# 6_-H3_MAIN.net
KiCad netlist of a schematic drawn in Altium Designer
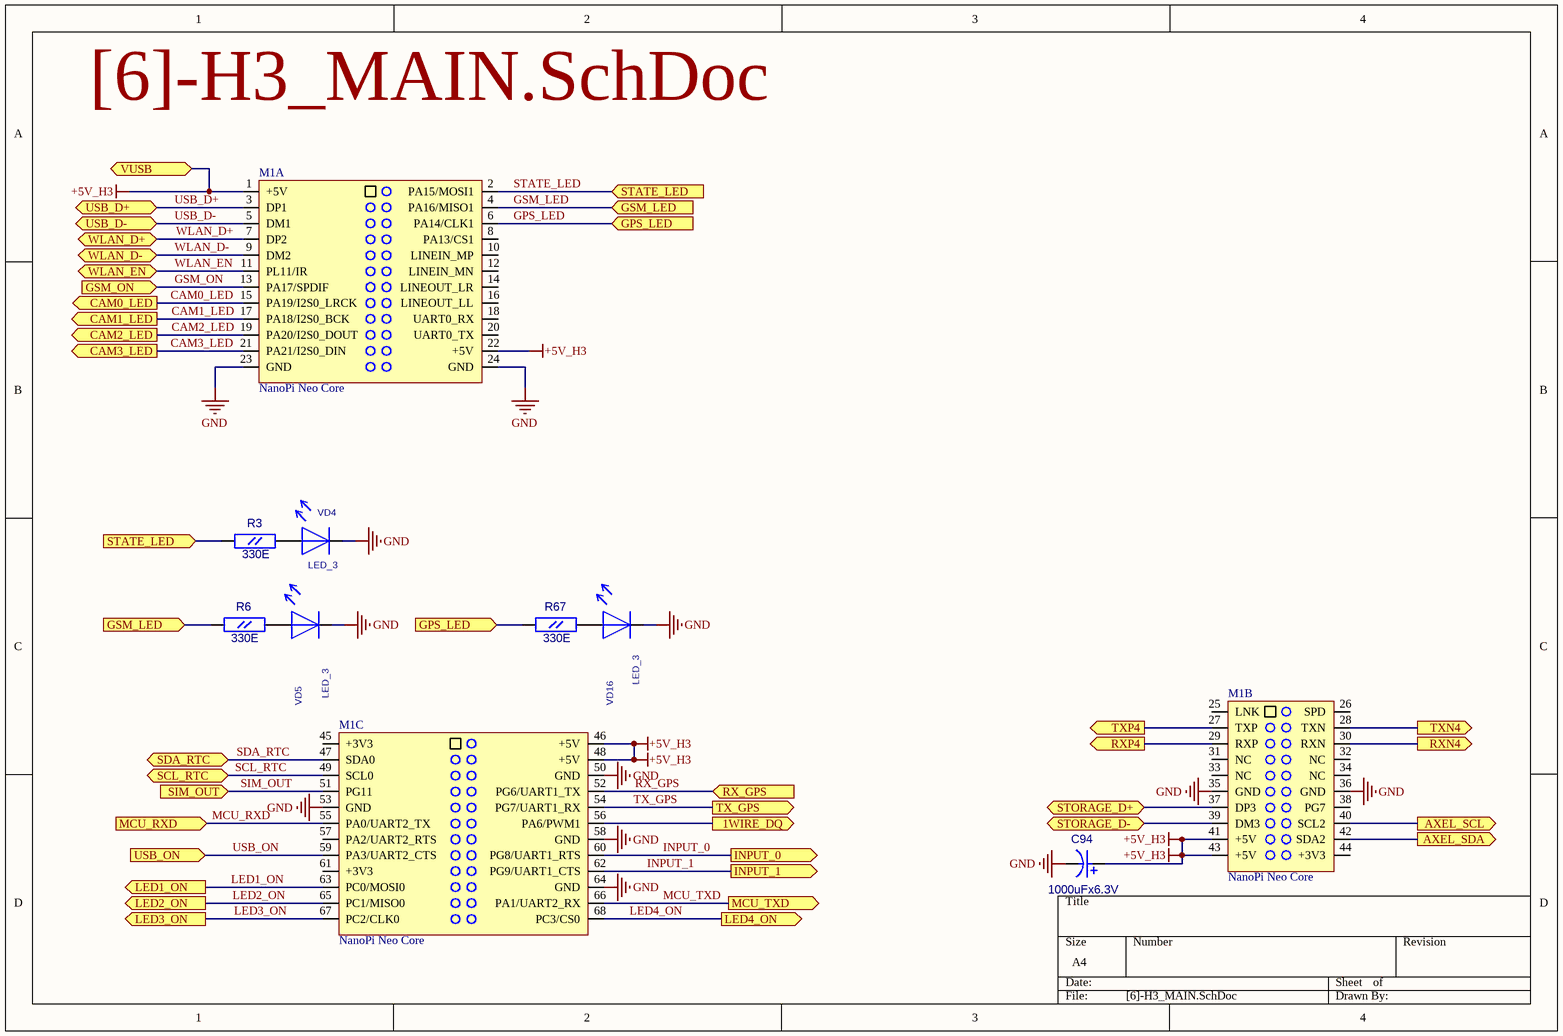
[diagram p0: [6]-H3_MAIN.SchDoc]

(export (version "E")
  (design (tool "Eeschema 10.0.6"))
  (components
    (comp (ref "C94")
      (value "1000uFx6.3V")
      (footprint "CC8X3.5")
      (description "Radial capacitor")
      (libsource (lib "fizik_lib (1)") (part "CAP_8mm"))
    )
    (comp (ref "M1")
      (value "NanoPi Neo Core")
      (footprint "NanoPiNeo_CORE")
      (description "Nano Pi Neo Core Allwinner H3 based embedded module")
      (libsource (lib "fizik_lib") (part "NanoPi Neo Core"))
    )
    (comp (ref "R3")
      (value "330E")
      (footprint "RC0603")
      (description "RC0603")
      (libsource (lib "fizik_lib (1)") (part "RC0603"))
    )
    (comp (ref "R6")
      (value "330E")
      (footprint "RC0603")
      (description "RC0603")
      (libsource (lib "fizik_lib (1)") (part "RC0603"))
    )
    (comp (ref "R67")
      (value "330E")
      (footprint "RC0603")
      (description "RC0603")
      (libsource (lib "fizik_lib (1)") (part "RC0603"))
    )
    (comp (ref "VD4") (value "LED_3") (footprint "LED3") (libsource (lib "fizik_lib (1)") (part "LED_3")))
    (comp (ref "VD5") (value "LED_3") (footprint "LED3") (libsource (lib "fizik_lib (1)") (part "LED_3")))
    (comp (ref "VD16") (value "LED_3") (footprint "LED3") (libsource (lib "fizik_lib (1)") (part "LED_3")))
  )
  (nets
    (net (code "1") (name "+5V_H3") (class "Default")
      (node (ref "C94") (pin "1") (pintype "passive"))
      (node (ref "M1") (pin "1") (pinfunction "+5V_1") (pintype "passive"))
      (node (ref "M1") (pin "22") (pinfunction "+5V_22") (pintype "passive"))
      (node (ref "M1") (pin "41") (pinfunction "+5V_41") (pintype "passive"))
      (node (ref "M1") (pin "43") (pinfunction "+5V_43") (pintype "passive"))
      (node (ref "M1") (pin "46") (pinfunction "+5V_46") (pintype "passive"))
      (node (ref "M1") (pin "48") (pinfunction "+5V_48") (pintype "passive"))
    )
    (net (code "2") (name "/1WIRE_DQ") (class "Default")
      (node (ref "M1") (pin "56") (pinfunction "PA6/PWM1_56") (pintype "passive"))
    )
    (net (code "3") (name "/AXEL_SCL") (class "Default")
      (node (ref "M1") (pin "40") (pinfunction "SCL2_40") (pintype "passive"))
    )
    (net (code "4") (name "/AXEL_SDA") (class "Default")
      (node (ref "M1") (pin "42") (pinfunction "SDA2_42") (pintype "passive"))
    )
    (net (code "5") (name "/CAM0_LED") (class "Default")
      (node (ref "M1") (pin "15") (pinfunction "PA19/I2S0_LRCK_15") (pintype "passive"))
    )
    (net (code "6") (name "/CAM1_LED") (class "Default")
      (node (ref "M1") (pin "17") (pinfunction "PA18/I2S0_BCK_17") (pintype "passive"))
    )
    (net (code "7") (name "/CAM2_LED") (class "Default")
      (node (ref "M1") (pin "19") (pinfunction "PA20/I2S0_DOUT_19") (pintype "passive"))
    )
    (net (code "8") (name "/CAM3_LED") (class "Default")
      (node (ref "M1") (pin "21") (pinfunction "PA21/I2S0_DIN_21") (pintype "passive"))
    )
    (net (code "9") (name "/GPS_LED") (class "Default")
      (node (ref "M1") (pin "6") (pinfunction "PA14/CLK1_6") (pintype "passive"))
      (node (ref "R67") (pin "1") (pinfunction "A_1") (pintype "passive"))
    )
    (net (code "10") (name "/GSM_LED") (class "Default")
      (node (ref "M1") (pin "4") (pinfunction "PA16/MISO1_4") (pintype "passive"))
      (node (ref "R6") (pin "1") (pinfunction "A_1") (pintype "passive"))
    )
    (net (code "11") (name "/GSM_ON") (class "Default")
      (node (ref "M1") (pin "13") (pinfunction "PA17/SPDIF_13") (pintype "passive"))
    )
    (net (code "12") (name "/INPUT_0") (class "Default")
      (node (ref "M1") (pin "60") (pinfunction "PG8/UART1_RTS_60") (pintype "passive"))
    )
    (net (code "13") (name "/INPUT_1") (class "Default")
      (node (ref "M1") (pin "62") (pinfunction "PG9/UART1_CTS_62") (pintype "passive"))
    )
    (net (code "14") (name "/LED1_ON") (class "Default")
      (node (ref "M1") (pin "63") (pinfunction "PC0/MOSI0_63") (pintype "passive"))
    )
    (net (code "15") (name "/LED2_ON") (class "Default")
      (node (ref "M1") (pin "65") (pinfunction "PC1/MISO0_65") (pintype "passive"))
    )
    (net (code "16") (name "/LED3_ON") (class "Default")
      (node (ref "M1") (pin "67") (pinfunction "PC2/CLK0_67") (pintype "passive"))
    )
    (net (code "17") (name "/LED4_ON") (class "Default")
      (node (ref "M1") (pin "68") (pinfunction "PC3/CS0_68") (pintype "passive"))
    )
    (net (code "18") (name "/MCU_RXD") (class "Default")
      (node (ref "M1") (pin "55") (pinfunction "PA0/UART2_TX_55") (pintype "passive"))
    )
    (net (code "19") (name "/MCU_TXD") (class "Default")
      (node (ref "M1") (pin "66") (pinfunction "PA1/UART2_RX_66") (pintype "passive"))
    )
    (net (code "20") (name "/RXN4") (class "Default")
      (node (ref "M1") (pin "30") (pinfunction "RXN_30") (pintype "passive"))
    )
    (net (code "21") (name "/RXP4") (class "Default")
      (node (ref "M1") (pin "29") (pinfunction "RXP_29") (pintype "passive"))
    )
    (net (code "22") (name "/RX_GPS") (class "Default")
      (node (ref "M1") (pin "52") (pinfunction "PG6/UART1_TX_52") (pintype "passive"))
    )
    (net (code "23") (name "/SCL_RTC") (class "Default")
      (node (ref "M1") (pin "49") (pinfunction "SCL0_49") (pintype "passive"))
    )
    (net (code "24") (name "/SDA_RTC") (class "Default")
      (node (ref "M1") (pin "47") (pinfunction "SDA0_47") (pintype "passive"))
    )
    (net (code "25") (name "/SIM_OUT") (class "Default")
      (node (ref "M1") (pin "51") (pinfunction "PG11_51") (pintype "passive"))
    )
    (net (code "26") (name "/STATE_LED") (class "Default")
      (node (ref "M1") (pin "2") (pinfunction "PA15/MOSI1_2") (pintype "passive"))
      (node (ref "R3") (pin "1") (pinfunction "A_1") (pintype "passive"))
    )
    (net (code "27") (name "/STORAGE_D+") (class "Default")
      (node (ref "M1") (pin "37") (pinfunction "DP3_37") (pintype "passive"))
    )
    (net (code "28") (name "/STORAGE_D-") (class "Default")
      (node (ref "M1") (pin "39") (pinfunction "DM3_39") (pintype "passive"))
    )
    (net (code "29") (name "/TXN4") (class "Default")
      (node (ref "M1") (pin "28") (pinfunction "TXN_28") (pintype "passive"))
    )
    (net (code "30") (name "/TXP4") (class "Default")
      (node (ref "M1") (pin "27") (pinfunction "TXP_27") (pintype "passive"))
    )
    (net (code "31") (name "/TX_GPS") (class "Default")
      (node (ref "M1") (pin "54") (pinfunction "PG7/UART1_RX_54") (pintype "passive"))
    )
    (net (code "32") (name "/USB_D+") (class "Default")
      (node (ref "M1") (pin "3") (pinfunction "DP1_3") (pintype "passive"))
    )
    (net (code "33") (name "/USB_D-") (class "Default")
      (node (ref "M1") (pin "5") (pinfunction "DM1_5") (pintype "passive"))
    )
    (net (code "34") (name "/USB_ON") (class "Default")
      (node (ref "M1") (pin "59") (pinfunction "PA3/UART2_CTS_59") (pintype "passive"))
    )
    (net (code "35") (name "/WLAN_D+") (class "Default")
      (node (ref "M1") (pin "7") (pinfunction "DP2_7") (pintype "passive"))
    )
    (net (code "36") (name "/WLAN_D-") (class "Default")
      (node (ref "M1") (pin "9") (pinfunction "DM2_9") (pintype "passive"))
    )
    (net (code "37") (name "/WLAN_EN") (class "Default")
      (node (ref "M1") (pin "11") (pinfunction "PL11/IR_11") (pintype "passive"))
    )
    (net (code "38") (name "GND") (class "Default")
      (node (ref "C94") (pin "2") (pintype "passive"))
      (node (ref "M1") (pin "23") (pinfunction "GND_23") (pintype "passive"))
      (node (ref "M1") (pin "24") (pinfunction "GND_24") (pintype "passive"))
      (node (ref "M1") (pin "35") (pinfunction "GND_35") (pintype "passive"))
      (node (ref "M1") (pin "36") (pinfunction "GND_36") (pintype "passive"))
      (node (ref "M1") (pin "50") (pinfunction "GND_50") (pintype "passive"))
      (node (ref "M1") (pin "53") (pinfunction "GND_53") (pintype "passive"))
      (node (ref "M1") (pin "58") (pinfunction "GND_58") (pintype "passive"))
      (node (ref "M1") (pin "64") (pinfunction "GND_64") (pintype "passive"))
      (node (ref "VD16") (pin "1") (pintype "passive"))
      (node (ref "VD4") (pin "1") (pintype "passive"))
      (node (ref "VD5") (pin "1") (pintype "passive"))
    )
    (net (code "39") (name "Net-(R3-B)") (class "Default")
      (node (ref "R3") (pin "2") (pinfunction "B_2") (pintype "passive"))
      (node (ref "VD4") (pin "2") (pintype "passive"))
    )
    (net (code "40") (name "Net-(R6-B)") (class "Default")
      (node (ref "R6") (pin "2") (pinfunction "B_2") (pintype "passive"))
      (node (ref "VD5") (pin "2") (pintype "passive"))
    )
    (net (code "41") (name "Net-(R67-B)") (class "Default")
      (node (ref "R67") (pin "2") (pinfunction "B_2") (pintype "passive"))
      (node (ref "VD16") (pin "2") (pintype "passive"))
    )
    (net (code "42") (name "unconnected-(M1A-LINEIN_MN-Pad12)") (class "Default")
      (node (ref "M1") (pin "12") (pinfunction "LINEIN_MN_12") (pintype "passive"))
    )
    (net (code "43") (name "unconnected-(M1A-LINEIN_MP-Pad10)") (class "Default")
      (node (ref "M1") (pin "10") (pinfunction "LINEIN_MP_10") (pintype "passive"))
    )
    (net (code "44") (name "unconnected-(M1A-LINEOUT_LL-Pad16)") (class "Default")
      (node (ref "M1") (pin "16") (pinfunction "LINEOUT_LL_16") (pintype "passive"))
    )
    (net (code "45") (name "unconnected-(M1A-LINEOUT_LR-Pad14)") (class "Default")
      (node (ref "M1") (pin "14") (pinfunction "LINEOUT_LR_14") (pintype "passive"))
    )
    (net (code "46") (name "unconnected-(M1A-PA13{slash}CS1-Pad8)") (class "Default")
      (node (ref "M1") (pin "8") (pinfunction "PA13/CS1_8") (pintype "passive"))
    )
    (net (code "47") (name "unconnected-(M1A-UART0_RX-Pad18)") (class "Default")
      (node (ref "M1") (pin "18") (pinfunction "UART0_RX_18") (pintype "passive"))
    )
    (net (code "48") (name "unconnected-(M1A-UART0_TX-Pad20)") (class "Default")
      (node (ref "M1") (pin "20") (pinfunction "UART0_TX_20") (pintype "passive"))
    )
    (net (code "49") (name "unconnected-(M1B-+3V3-Pad44)") (class "Default")
      (node (ref "M1") (pin "44") (pinfunction "+3V3_44") (pintype "passive"))
    )
    (net (code "50") (name "unconnected-(M1B-LNK-Pad25)") (class "Default")
      (node (ref "M1") (pin "25") (pinfunction "LNK_25") (pintype "passive"))
    )
    (net (code "51") (name "unconnected-(M1B-NC-Pad31)") (class "Default")
      (node (ref "M1") (pin "31") (pinfunction "NC_31") (pintype "passive"))
    )
    (net (code "52") (name "unconnected-(M1B-NC-Pad32)") (class "Default")
      (node (ref "M1") (pin "32") (pinfunction "NC_32") (pintype "passive"))
    )
    (net (code "53") (name "unconnected-(M1B-NC-Pad33)") (class "Default")
      (node (ref "M1") (pin "33") (pinfunction "NC_33") (pintype "passive"))
    )
    (net (code "54") (name "unconnected-(M1B-NC-Pad34)") (class "Default")
      (node (ref "M1") (pin "34") (pinfunction "NC_34") (pintype "passive"))
    )
    (net (code "55") (name "unconnected-(M1B-PG7-Pad38)") (class "Default")
      (node (ref "M1") (pin "38") (pinfunction "PG7_38") (pintype "passive"))
    )
    (net (code "56") (name "unconnected-(M1B-SPD-Pad26)") (class "Default")
      (node (ref "M1") (pin "26") (pinfunction "SPD_26") (pintype "passive"))
    )
    (net (code "57") (name "unconnected-(M1C-+3V3-Pad45)") (class "Default")
      (node (ref "M1") (pin "45") (pinfunction "+3V3_45") (pintype "passive"))
    )
    (net (code "58") (name "unconnected-(M1C-+3V3-Pad61)") (class "Default")
      (node (ref "M1") (pin "61") (pinfunction "+3V3_61") (pintype "passive"))
    )
    (net (code "59") (name "unconnected-(M1C-PA2{slash}UART2_RTS-Pad57)") (class "Default")
      (node (ref "M1") (pin "57") (pinfunction "PA2/UART2_RTS_57") (pintype "passive"))
    )
  )
)
